# adc-amp.net
KiCad netlist of a schematic drawn in Altium Designer
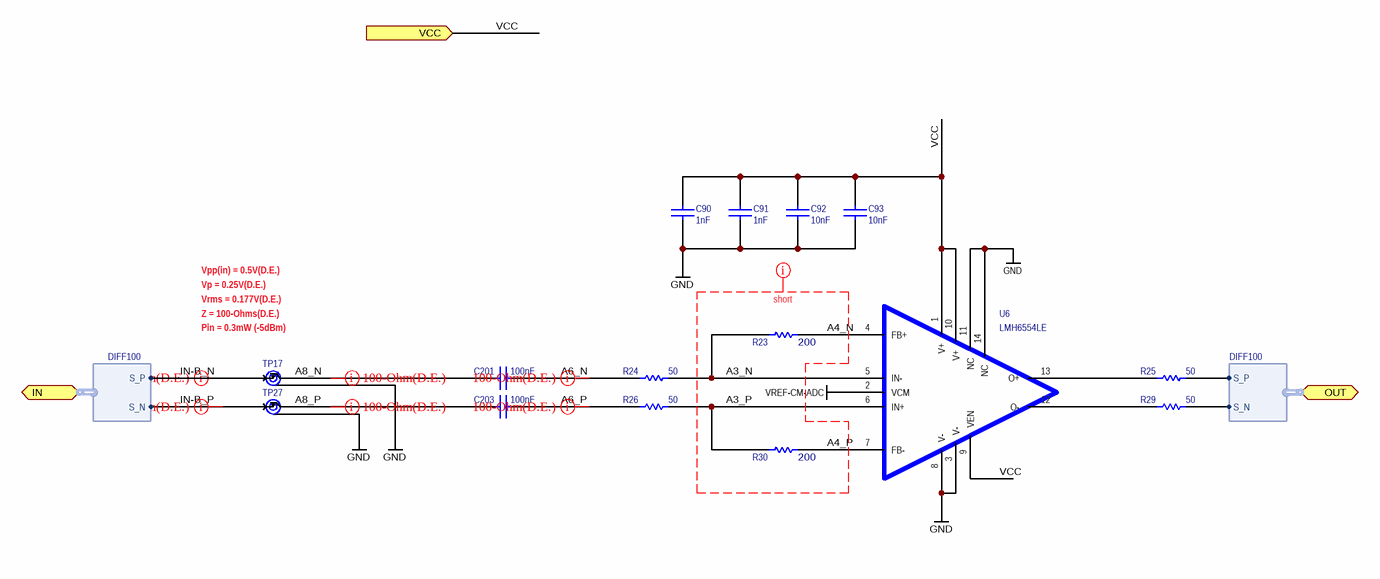
[diagram p0: adc-amp.SchDoc]

(export (version "E")
  (design (tool "Eeschema 10.0.6"))
  (components
    (comp (ref "C90")
      (value "1nF")
      (footprint "CAPC100X50X55L25N")
      (description "Ceramic Capacitor 1nF ±5% 50V NP0 0402")
      (fields (field (name "VOLTAGE") "50V") (field (name "MANUFACTURER") "TDK"))
      (libsource (lib "Graviton") (part "CAP 0402"))
    )
    (comp (ref "C91")
      (value "1nF")
      (footprint "CAPC100X50X55L25N")
      (description "Ceramic Capacitor 1nF ±5% 50V NP0 0402")
      (fields (field (name "VOLTAGE") "50V") (field (name "MANUFACTURER") "TDK"))
      (libsource (lib "Graviton") (part "CAP 0402"))
    )
    (comp (ref "C92")
      (value "10nF")
      (footprint "CAPC100X50X55L25N")
      (description "Ceramic Capacitor 10nF ±10% 50V X7R 0402")
      (fields (field (name "VOLTAGE") "50V") (field (name "MANUFACTURER") "Murata"))
      (libsource (lib "Graviton") (part "CAP 0402"))
    )
    (comp (ref "C93")
      (value "10nF")
      (footprint "CAPC100X50X55L25N")
      (description "Ceramic Capacitor 10nF ±10% 50V X7R 0402")
      (fields (field (name "VOLTAGE") "50V") (field (name "MANUFACTURER") "Murata"))
      (libsource (lib "Graviton") (part "CAP 0402"))
    )
    (comp (ref "C201")
      (value "100nF")
      (footprint "CAPC100X50X55L25N")
      (description "Ceramic Capacitor 100nF ±10% 16V X7R 0402")
      (fields (field (name "VOLTAGE") "16V") (field (name "MANUFACTURER") "Murata"))
      (libsource (lib "Graviton") (part "CAP 0402"))
    )
    (comp (ref "C203")
      (value "100nF")
      (footprint "CAPC100X50X55L25N")
      (description "Ceramic Capacitor 100nF ±10% 16V X7R 0402")
      (fields (field (name "VOLTAGE") "16V") (field (name "MANUFACTURER") "Murata"))
      (libsource (lib "Graviton") (part "CAP 0402"))
    )
    (comp (ref "R23")
      (value "200")
      (footprint "generic:RESC1608X55N")
      (description "Thin Film Resistor 200 Ohm ±1% 0603")
      (fields (field (name "MANUFACTURER") "Vishay") (field (name "TOLERANCE") "±1%"))
      (libsource (lib "Graviton") (part "RES 0603"))
    )
    (comp (ref "R24")
      (value "50")
      (footprint "generic:RESC1005X40N")
      (description "Thin Film RF Resistor 50 Ohm ±0.1% 0402")
      (fields (field (name "MANUFACTURER") "Vishay") (field (name "TOLERANCE") "±0.1%"))
      (libsource (lib "Graviton") (part "RES 0603"))
    )
    (comp (ref "R25")
      (value "50")
      (footprint "generic:RESC1005X40N")
      (description "Thin Film RF Resistor 50 Ohm ±0.1% 0402")
      (fields (field (name "MANUFACTURER") "Vishay") (field (name "TOLERANCE") "±0.1%"))
      (libsource (lib "Graviton") (part "RES 0603"))
    )
    (comp (ref "R26")
      (value "50")
      (footprint "generic:RESC1005X40N")
      (description "Thin Film RF Resistor 50 Ohm ±0.1% 0402")
      (fields (field (name "MANUFACTURER") "Vishay") (field (name "TOLERANCE") "±0.1%"))
      (libsource (lib "Graviton") (part "RES 0603"))
    )
    (comp (ref "R29")
      (value "50")
      (footprint "generic:RESC1005X40N")
      (description "Thin Film RF Resistor 50 Ohm ±0.1% 0402")
      (fields (field (name "MANUFACTURER") "Vishay") (field (name "TOLERANCE") "±0.1%"))
      (libsource (lib "Graviton") (part "RES 0603"))
    )
    (comp (ref "R30")
      (value "200")
      (footprint "generic:RESC1608X55N")
      (description "Thin Film Resistor 200 Ohm ±1% 0603")
      (fields (field (name "MANUFACTURER") "Vishay") (field (name "TOLERANCE") "±1%"))
      (libsource (lib "Graviton") (part "RES 0603"))
    )
    (comp (ref "TP17")
      (value "MS-180(20)")
      (footprint "MS-180(20)")
      (description "Coaxial Connector Switch")
      (fields (field (name "MANUFACTURER") "Hirose"))
      (libsource (lib "hirose") (part "MS-180(20)"))
    )
    (comp (ref "TP27")
      (value "MS-180(20)")
      (footprint "MS-180(20)")
      (description "Coaxial Connector Switch")
      (fields (field (name "MANUFACTURER") "Hirose"))
      (libsource (lib "hirose") (part "MS-180(20)"))
    )
    (comp (ref "U6")
      (value "LMH6554LE")
      (footprint "texas_instruments:NHJ0014A")
      (description "2.8 GHz Ultra Linear Fully Differential Amplifier")
      (fields (field (name "MANUFACTURER") "Texas Instruments"))
      (libsource (lib "ti") (part "LMH6554LE"))
    )
  )
  (nets
    (net (code "2") (name "/A3_N") (class "Default")
      (node (ref "R23") (pin "1") (pinfunction "1_1") (pintype "passive"))
      (node (ref "R24") (pin "2") (pinfunction "2_2") (pintype "passive"))
      (node (ref "U6") (pin "5") (pinfunction "IN-_5") (pintype "passive"))
    )
    (net (code "3") (name "/A3_P") (class "Default")
      (node (ref "R26") (pin "2") (pinfunction "2_2") (pintype "passive"))
      (node (ref "R30") (pin "1") (pinfunction "1_1") (pintype "passive"))
      (node (ref "U6") (pin "6") (pinfunction "IN+_6") (pintype "passive"))
    )
    (net (code "4") (name "/A4_N") (class "Default")
      (node (ref "R23") (pin "2") (pinfunction "2_2") (pintype "passive"))
      (node (ref "U6") (pin "4") (pinfunction "FB+_4") (pintype "passive"))
    )
    (net (code "5") (name "/A4_P") (class "Default")
      (node (ref "R30") (pin "2") (pinfunction "2_2") (pintype "passive"))
      (node (ref "U6") (pin "7") (pinfunction "FB-_7") (pintype "passive"))
    )
    (net (code "6") (name "/A6_N") (class "Default")
      (node (ref "C201") (pin "2") (pinfunction "2_2") (pintype "passive"))
      (node (ref "R24") (pin "1") (pinfunction "1_1") (pintype "passive"))
    )
    (net (code "7") (name "/A6_P") (class "Default")
      (node (ref "C203") (pin "2") (pinfunction "2_2") (pintype "passive"))
      (node (ref "R26") (pin "1") (pinfunction "1_1") (pintype "passive"))
    )
    (net (code "8") (name "/A8_N") (class "Default")
      (node (ref "C201") (pin "1") (pinfunction "1_1") (pintype "passive"))
      (node (ref "TP17") (pin "A") (pinfunction "OUT_A") (pintype "passive"))
    )
    (net (code "9") (name "/A8_P") (class "Default")
      (node (ref "C203") (pin "1") (pinfunction "1_1") (pintype "passive"))
      (node (ref "TP27") (pin "A") (pinfunction "OUT_A") (pintype "passive"))
    )
    (net (code "10") (name "/IN-B_N") (class "Default")
      (node (ref "TP17") (pin "C") (pinfunction "IN_C") (pintype "passive"))
    )
    (net (code "11") (name "/IN-B_P") (class "Default")
      (node (ref "TP27") (pin "C") (pinfunction "IN_C") (pintype "passive"))
    )
    (net (code "12") (name "/VCC") (class "Default")
      (node (ref "C90") (pin "2") (pinfunction "2_2") (pintype "passive"))
      (node (ref "C91") (pin "2") (pinfunction "2_2") (pintype "passive"))
      (node (ref "C92") (pin "2") (pinfunction "2_2") (pintype "passive"))
      (node (ref "C93") (pin "2") (pinfunction "2_2") (pintype "passive"))
      (node (ref "U6") (pin "1") (pinfunction "V+_1") (pintype "passive"))
      (node (ref "U6") (pin "10") (pinfunction "V+_10") (pintype "passive"))
      (node (ref "U6") (pin "9") (pinfunction "VEN_9") (pintype "passive"))
    )
    (net (code "14") (name "GND") (class "Default")
      (node (ref "C90") (pin "1") (pinfunction "1_1") (pintype "passive"))
      (node (ref "C91") (pin "1") (pinfunction "1_1") (pintype "passive"))
      (node (ref "C92") (pin "1") (pinfunction "1_1") (pintype "passive"))
      (node (ref "C93") (pin "1") (pinfunction "1_1") (pintype "passive"))
      (node (ref "TP17") (pin "G") (pinfunction "GND_G") (pintype "passive"))
      (node (ref "TP27") (pin "G") (pinfunction "GND_G") (pintype "passive"))
      (node (ref "U6") (pin "11") (pinfunction "NC_11") (pintype "passive"))
      (node (ref "U6") (pin "14") (pinfunction "NC_14") (pintype "passive"))
      (node (ref "U6") (pin "3") (pinfunction "V-_3") (pintype "passive"))
      (node (ref "U6") (pin "8") (pinfunction "V-_8") (pintype "passive"))
    )
    (net (code "15") (name "Net-(U6-O+)") (class "Default")
      (node (ref "R25") (pin "1") (pinfunction "1_1") (pintype "passive"))
      (node (ref "U6") (pin "13") (pinfunction "O+_13") (pintype "passive"))
    )
    (net (code "16") (name "Net-(U6-O-)") (class "Default")
      (node (ref "R29") (pin "1") (pinfunction "1_1") (pintype "passive"))
      (node (ref "U6") (pin "12") (pinfunction "O-_12") (pintype "passive"))
    )
    (net (code "17") (name "VREF-CM-ADC") (class "Default")
      (node (ref "U6") (pin "2") (pinfunction "VCM_2") (pintype "passive"))
    )
    (net (code "18") (name "unconnected-(R25-Pad2)") (class "Default")
      (node (ref "R25") (pin "2") (pinfunction "2_2") (pintype "passive"))
    )
    (net (code "19") (name "unconnected-(R29-Pad2)") (class "Default")
      (node (ref "R29") (pin "2") (pinfunction "2_2") (pintype "passive"))
    )
  )
)
